# Electrotactile_Schematic.net
KiCad netlist of a schematic drawn in EAGLE
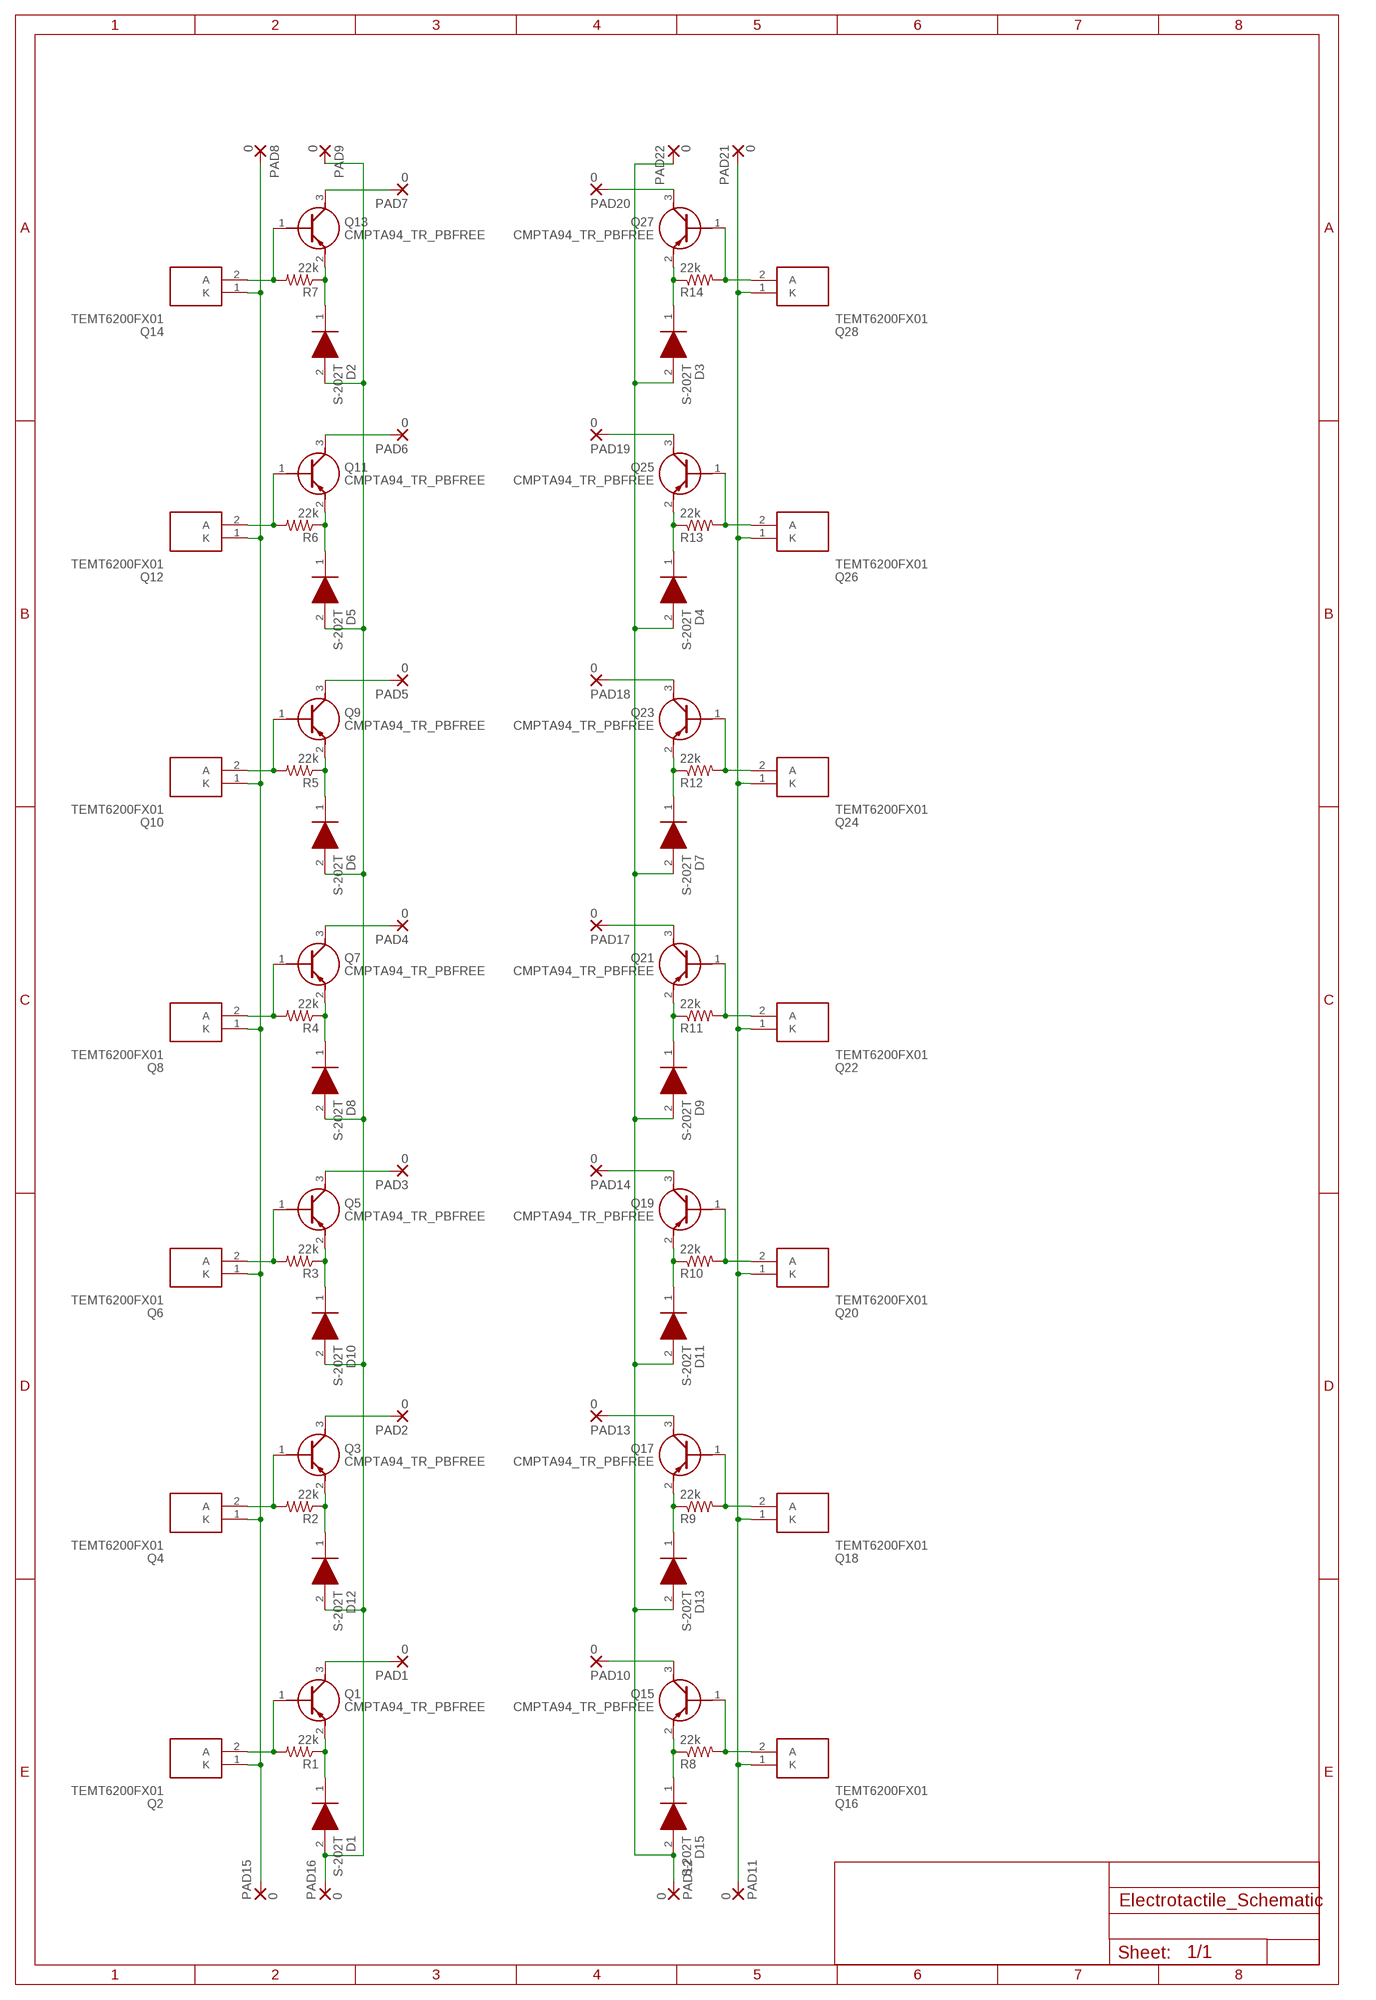
[diagram p0: schematic, sheet 1]

(export (version "E")
  (design (tool "Eeschema 10.0.6"))
  (components
    (comp (ref "D1")
      (value "S-202T")
      (footprint "eagle-import:SODFL3516X70N")
      (fields (field (name "MOUSER_PART_NUMBER") "954-S-202T"))
      (libsource (lib "eagle-import") (part "S-202T"))
    )
    (comp (ref "D2")
      (value "S-202T")
      (footprint "eagle-import:SODFL3516X70N")
      (fields (field (name "MOUSER_PART_NUMBER") "954-S-202T"))
      (libsource (lib "eagle-import") (part "S-202T"))
    )
    (comp (ref "D3")
      (value "S-202T")
      (footprint "eagle-import:SODFL3516X70N")
      (fields (field (name "MOUSER_PART_NUMBER") "954-S-202T"))
      (libsource (lib "eagle-import") (part "S-202T"))
    )
    (comp (ref "D4")
      (value "S-202T")
      (footprint "eagle-import:SODFL3516X70N")
      (fields (field (name "MOUSER_PART_NUMBER") "954-S-202T"))
      (libsource (lib "eagle-import") (part "S-202T"))
    )
    (comp (ref "D5")
      (value "S-202T")
      (footprint "eagle-import:SODFL3516X70N")
      (fields (field (name "MOUSER_PART_NUMBER") "954-S-202T"))
      (libsource (lib "eagle-import") (part "S-202T"))
    )
    (comp (ref "D6")
      (value "S-202T")
      (footprint "eagle-import:SODFL3516X70N")
      (fields (field (name "MOUSER_PART_NUMBER") "954-S-202T"))
      (libsource (lib "eagle-import") (part "S-202T"))
    )
    (comp (ref "D7")
      (value "S-202T")
      (footprint "eagle-import:SODFL3516X70N")
      (fields (field (name "MOUSER_PART_NUMBER") "954-S-202T"))
      (libsource (lib "eagle-import") (part "S-202T"))
    )
    (comp (ref "D8")
      (value "S-202T")
      (footprint "eagle-import:SODFL3516X70N")
      (fields (field (name "MOUSER_PART_NUMBER") "954-S-202T"))
      (libsource (lib "eagle-import") (part "S-202T"))
    )
    (comp (ref "D9")
      (value "S-202T")
      (footprint "eagle-import:SODFL3516X70N")
      (fields (field (name "MOUSER_PART_NUMBER") "954-S-202T"))
      (libsource (lib "eagle-import") (part "S-202T"))
    )
    (comp (ref "D10")
      (value "S-202T")
      (footprint "eagle-import:SODFL3516X70N")
      (fields (field (name "MOUSER_PART_NUMBER") "954-S-202T"))
      (libsource (lib "eagle-import") (part "S-202T"))
    )
    (comp (ref "D11")
      (value "S-202T")
      (footprint "eagle-import:SODFL3516X70N")
      (fields (field (name "MOUSER_PART_NUMBER") "954-S-202T"))
      (libsource (lib "eagle-import") (part "S-202T"))
    )
    (comp (ref "D12")
      (value "S-202T")
      (footprint "eagle-import:SODFL3516X70N")
      (fields (field (name "MOUSER_PART_NUMBER") "954-S-202T"))
      (libsource (lib "eagle-import") (part "S-202T"))
    )
    (comp (ref "D13")
      (value "S-202T")
      (footprint "eagle-import:SODFL3516X70N")
      (fields (field (name "MOUSER_PART_NUMBER") "954-S-202T"))
      (libsource (lib "eagle-import") (part "S-202T"))
    )
    (comp (ref "D15")
      (value "S-202T")
      (footprint "eagle-import:SODFL3516X70N")
      (fields (field (name "MOUSER_PART_NUMBER") "954-S-202T"))
      (libsource (lib "eagle-import") (part "S-202T"))
    )
    (comp (ref "PAD1")
      (value "0")
      (footprint "eagle-import:1,6_0,8")
      (libsource (lib "eagle-import") (part "1,6/0,8"))
    )
    (comp (ref "PAD2")
      (value "0")
      (footprint "eagle-import:1,6_0,8")
      (libsource (lib "eagle-import") (part "1,6/0,8"))
    )
    (comp (ref "PAD3")
      (value "0")
      (footprint "eagle-import:1,6_0,8")
      (libsource (lib "eagle-import") (part "1,6/0,8"))
    )
    (comp (ref "PAD4")
      (value "0")
      (footprint "eagle-import:1,6_0,8")
      (libsource (lib "eagle-import") (part "1,6/0,8"))
    )
    (comp (ref "PAD5")
      (value "0")
      (footprint "eagle-import:1,6_0,8")
      (libsource (lib "eagle-import") (part "1,6/0,8"))
    )
    (comp (ref "PAD6")
      (value "0")
      (footprint "eagle-import:1,6_0,8")
      (libsource (lib "eagle-import") (part "1,6/0,8"))
    )
    (comp (ref "PAD7")
      (value "0")
      (footprint "eagle-import:1,6_0,8")
      (libsource (lib "eagle-import") (part "1,6/0,8"))
    )
    (comp (ref "PAD8")
      (value "0")
      (footprint "eagle-import:1,6_0,8")
      (libsource (lib "eagle-import") (part "1,6/0,8"))
    )
    (comp (ref "PAD9")
      (value "0")
      (footprint "eagle-import:1,6_0,8")
      (libsource (lib "eagle-import") (part "1,6/0,8"))
    )
    (comp (ref "PAD10")
      (value "0")
      (footprint "eagle-import:1,6_0,8")
      (libsource (lib "eagle-import") (part "1,6/0,8"))
    )
    (comp (ref "PAD11")
      (value "0")
      (footprint "eagle-import:1,6_0,8")
      (libsource (lib "eagle-import") (part "1,6/0,8"))
    )
    (comp (ref "PAD12")
      (value "0")
      (footprint "eagle-import:1,6_0,8")
      (libsource (lib "eagle-import") (part "1,6/0,8"))
    )
    (comp (ref "PAD13")
      (value "0")
      (footprint "eagle-import:1,6_0,8")
      (libsource (lib "eagle-import") (part "1,6/0,8"))
    )
    (comp (ref "PAD14")
      (value "0")
      (footprint "eagle-import:1,6_0,8")
      (libsource (lib "eagle-import") (part "1,6/0,8"))
    )
    (comp (ref "PAD15")
      (value "0")
      (footprint "eagle-import:1,6_0,8")
      (libsource (lib "eagle-import") (part "1,6/0,8"))
    )
    (comp (ref "PAD16")
      (value "0")
      (footprint "eagle-import:1,6_0,8")
      (libsource (lib "eagle-import") (part "1,6/0,8"))
    )
    (comp (ref "PAD17")
      (value "0")
      (footprint "eagle-import:1,6_0,8")
      (libsource (lib "eagle-import") (part "1,6/0,8"))
    )
    (comp (ref "PAD18")
      (value "0")
      (footprint "eagle-import:1,6_0,8")
      (libsource (lib "eagle-import") (part "1,6/0,8"))
    )
    (comp (ref "PAD19")
      (value "0")
      (footprint "eagle-import:1,6_0,8")
      (libsource (lib "eagle-import") (part "1,6/0,8"))
    )
    (comp (ref "PAD20")
      (value "0")
      (footprint "eagle-import:1,6_0,8")
      (libsource (lib "eagle-import") (part "1,6/0,8"))
    )
    (comp (ref "PAD21")
      (value "0")
      (footprint "eagle-import:1,6_0,8")
      (libsource (lib "eagle-import") (part "1,6/0,8"))
    )
    (comp (ref "PAD22")
      (value "0")
      (footprint "eagle-import:1,6_0,8")
      (libsource (lib "eagle-import") (part "1,6/0,8"))
    )
    (comp (ref "Q1")
      (value "CMPTA94_TR_PBFREE")
      (footprint "eagle-import:SOT95P230X109-3N")
      (fields (field (name "MANUFACTURER_PART_NUMBER") "CMPTA94 TR PBFREE"))
      (libsource (lib "eagle-import") (part "CMPTA94_TR_PBFREE"))
    )
    (comp (ref "Q2")
      (value "TEMT6200FX01")
      (footprint "eagle-import:LEDC2012X95N")
      (fields (field (name "MOUSER_PART_NUMBER") "782-TEMT6200F"))
      (libsource (lib "eagle-import") (part "TEMT6200FX01"))
    )
    (comp (ref "Q3")
      (value "CMPTA94_TR_PBFREE")
      (footprint "eagle-import:SOT95P230X109-3N")
      (fields (field (name "MANUFACTURER_PART_NUMBER") "CMPTA94 TR PBFREE"))
      (libsource (lib "eagle-import") (part "CMPTA94_TR_PBFREE"))
    )
    (comp (ref "Q4")
      (value "TEMT6200FX01")
      (footprint "eagle-import:LEDC2012X95N")
      (fields (field (name "MOUSER_PART_NUMBER") "782-TEMT6200F"))
      (libsource (lib "eagle-import") (part "TEMT6200FX01"))
    )
    (comp (ref "Q5")
      (value "CMPTA94_TR_PBFREE")
      (footprint "eagle-import:SOT95P230X109-3N")
      (fields (field (name "MANUFACTURER_PART_NUMBER") "CMPTA94 TR PBFREE"))
      (libsource (lib "eagle-import") (part "CMPTA94_TR_PBFREE"))
    )
    (comp (ref "Q6")
      (value "TEMT6200FX01")
      (footprint "eagle-import:LEDC2012X95N")
      (fields (field (name "MOUSER_PART_NUMBER") "782-TEMT6200F"))
      (libsource (lib "eagle-import") (part "TEMT6200FX01"))
    )
    (comp (ref "Q7")
      (value "CMPTA94_TR_PBFREE")
      (footprint "eagle-import:SOT95P230X109-3N")
      (fields (field (name "MANUFACTURER_PART_NUMBER") "CMPTA94 TR PBFREE"))
      (libsource (lib "eagle-import") (part "CMPTA94_TR_PBFREE"))
    )
    (comp (ref "Q8")
      (value "TEMT6200FX01")
      (footprint "eagle-import:LEDC2012X95N")
      (fields (field (name "MOUSER_PART_NUMBER") "782-TEMT6200F"))
      (libsource (lib "eagle-import") (part "TEMT6200FX01"))
    )
    (comp (ref "Q9")
      (value "CMPTA94_TR_PBFREE")
      (footprint "eagle-import:SOT95P230X109-3N")
      (fields (field (name "MANUFACTURER_PART_NUMBER") "CMPTA94 TR PBFREE"))
      (libsource (lib "eagle-import") (part "CMPTA94_TR_PBFREE"))
    )
    (comp (ref "Q10")
      (value "TEMT6200FX01")
      (footprint "eagle-import:LEDC2012X95N")
      (fields (field (name "MOUSER_PART_NUMBER") "782-TEMT6200F"))
      (libsource (lib "eagle-import") (part "TEMT6200FX01"))
    )
    (comp (ref "Q11")
      (value "CMPTA94_TR_PBFREE")
      (footprint "eagle-import:SOT95P230X109-3N")
      (fields (field (name "MANUFACTURER_PART_NUMBER") "CMPTA94 TR PBFREE"))
      (libsource (lib "eagle-import") (part "CMPTA94_TR_PBFREE"))
    )
    (comp (ref "Q12")
      (value "TEMT6200FX01")
      (footprint "eagle-import:LEDC2012X95N")
      (fields (field (name "MOUSER_PART_NUMBER") "782-TEMT6200F"))
      (libsource (lib "eagle-import") (part "TEMT6200FX01"))
    )
    (comp (ref "Q13")
      (value "CMPTA94_TR_PBFREE")
      (footprint "eagle-import:SOT95P230X109-3N")
      (fields (field (name "MANUFACTURER_PART_NUMBER") "CMPTA94 TR PBFREE"))
      (libsource (lib "eagle-import") (part "CMPTA94_TR_PBFREE"))
    )
    (comp (ref "Q14")
      (value "TEMT6200FX01")
      (footprint "eagle-import:LEDC2012X95N")
      (fields (field (name "MOUSER_PART_NUMBER") "782-TEMT6200F"))
      (libsource (lib "eagle-import") (part "TEMT6200FX01"))
    )
    (comp (ref "Q15")
      (value "CMPTA94_TR_PBFREE")
      (footprint "eagle-import:SOT95P230X109-3N")
      (fields (field (name "MANUFACTURER_PART_NUMBER") "CMPTA94 TR PBFREE"))
      (libsource (lib "eagle-import") (part "CMPTA94_TR_PBFREE"))
    )
    (comp (ref "Q16")
      (value "TEMT6200FX01")
      (footprint "eagle-import:LEDC2012X95N")
      (fields (field (name "MOUSER_PART_NUMBER") "782-TEMT6200F"))
      (libsource (lib "eagle-import") (part "TEMT6200FX01"))
    )
    (comp (ref "Q17")
      (value "CMPTA94_TR_PBFREE")
      (footprint "eagle-import:SOT95P230X109-3N")
      (fields (field (name "MANUFACTURER_PART_NUMBER") "CMPTA94 TR PBFREE"))
      (libsource (lib "eagle-import") (part "CMPTA94_TR_PBFREE"))
    )
    (comp (ref "Q18")
      (value "TEMT6200FX01")
      (footprint "eagle-import:LEDC2012X95N")
      (fields (field (name "MOUSER_PART_NUMBER") "782-TEMT6200F"))
      (libsource (lib "eagle-import") (part "TEMT6200FX01"))
    )
    (comp (ref "Q19")
      (value "CMPTA94_TR_PBFREE")
      (footprint "eagle-import:SOT95P230X109-3N")
      (fields (field (name "MANUFACTURER_PART_NUMBER") "CMPTA94 TR PBFREE"))
      (libsource (lib "eagle-import") (part "CMPTA94_TR_PBFREE"))
    )
    (comp (ref "Q20")
      (value "TEMT6200FX01")
      (footprint "eagle-import:LEDC2012X95N")
      (fields (field (name "MOUSER_PART_NUMBER") "782-TEMT6200F"))
      (libsource (lib "eagle-import") (part "TEMT6200FX01"))
    )
    (comp (ref "Q21")
      (value "CMPTA94_TR_PBFREE")
      (footprint "eagle-import:SOT95P230X109-3N")
      (fields (field (name "MANUFACTURER_PART_NUMBER") "CMPTA94 TR PBFREE"))
      (libsource (lib "eagle-import") (part "CMPTA94_TR_PBFREE"))
    )
    (comp (ref "Q22")
      (value "TEMT6200FX01")
      (footprint "eagle-import:LEDC2012X95N")
      (fields (field (name "MOUSER_PART_NUMBER") "782-TEMT6200F"))
      (libsource (lib "eagle-import") (part "TEMT6200FX01"))
    )
    (comp (ref "Q23")
      (value "CMPTA94_TR_PBFREE")
      (footprint "eagle-import:SOT95P230X109-3N")
      (fields (field (name "MANUFACTURER_PART_NUMBER") "CMPTA94 TR PBFREE"))
      (libsource (lib "eagle-import") (part "CMPTA94_TR_PBFREE"))
    )
    (comp (ref "Q24")
      (value "TEMT6200FX01")
      (footprint "eagle-import:LEDC2012X95N")
      (fields (field (name "MOUSER_PART_NUMBER") "782-TEMT6200F"))
      (libsource (lib "eagle-import") (part "TEMT6200FX01"))
    )
    (comp (ref "Q25")
      (value "CMPTA94_TR_PBFREE")
      (footprint "eagle-import:SOT95P230X109-3N")
      (fields (field (name "MANUFACTURER_PART_NUMBER") "CMPTA94 TR PBFREE"))
      (libsource (lib "eagle-import") (part "CMPTA94_TR_PBFREE"))
    )
    (comp (ref "Q26")
      (value "TEMT6200FX01")
      (footprint "eagle-import:LEDC2012X95N")
      (fields (field (name "MOUSER_PART_NUMBER") "782-TEMT6200F"))
      (libsource (lib "eagle-import") (part "TEMT6200FX01"))
    )
    (comp (ref "Q27")
      (value "CMPTA94_TR_PBFREE")
      (footprint "eagle-import:SOT95P230X109-3N")
      (fields (field (name "MANUFACTURER_PART_NUMBER") "CMPTA94 TR PBFREE"))
      (libsource (lib "eagle-import") (part "CMPTA94_TR_PBFREE"))
    )
    (comp (ref "Q28")
      (value "TEMT6200FX01")
      (footprint "eagle-import:LEDC2012X95N")
      (fields (field (name "MOUSER_PART_NUMBER") "782-TEMT6200F"))
      (libsource (lib "eagle-import") (part "TEMT6200FX01"))
    )
    (comp (ref "R1")
      (value "22k")
      (footprint "eagle-import:R0805")
      (libsource (lib "eagle-import") (part "R-US_R0805"))
    )
    (comp (ref "R2")
      (value "22k")
      (footprint "eagle-import:R0805")
      (libsource (lib "eagle-import") (part "R-US_R0805"))
    )
    (comp (ref "R3")
      (value "22k")
      (footprint "eagle-import:R0805")
      (libsource (lib "eagle-import") (part "R-US_R0805"))
    )
    (comp (ref "R4")
      (value "22k")
      (footprint "eagle-import:R0805")
      (libsource (lib "eagle-import") (part "R-US_R0805"))
    )
    (comp (ref "R5")
      (value "22k")
      (footprint "eagle-import:R0805")
      (libsource (lib "eagle-import") (part "R-US_R0805"))
    )
    (comp (ref "R6")
      (value "22k")
      (footprint "eagle-import:R0805")
      (libsource (lib "eagle-import") (part "R-US_R0805"))
    )
    (comp (ref "R7")
      (value "22k")
      (footprint "eagle-import:R0805")
      (libsource (lib "eagle-import") (part "R-US_R0805"))
    )
    (comp (ref "R8")
      (value "22k")
      (footprint "eagle-import:R0805")
      (libsource (lib "eagle-import") (part "R-US_R0805"))
    )
    (comp (ref "R9")
      (value "22k")
      (footprint "eagle-import:R0805")
      (libsource (lib "eagle-import") (part "R-US_R0805"))
    )
    (comp (ref "R10")
      (value "22k")
      (footprint "eagle-import:R0805")
      (libsource (lib "eagle-import") (part "R-US_R0805"))
    )
    (comp (ref "R11")
      (value "22k")
      (footprint "eagle-import:R0805")
      (libsource (lib "eagle-import") (part "R-US_R0805"))
    )
    (comp (ref "R12")
      (value "22k")
      (footprint "eagle-import:R0805")
      (libsource (lib "eagle-import") (part "R-US_R0805"))
    )
    (comp (ref "R13")
      (value "22k")
      (footprint "eagle-import:R0805")
      (libsource (lib "eagle-import") (part "R-US_R0805"))
    )
    (comp (ref "R14")
      (value "22k")
      (footprint "eagle-import:R0805")
      (libsource (lib "eagle-import") (part "R-US_R0805"))
    )
  )
  (nets
    (net (code "1") (name "Net-(D1-A)") (class "Default")
      (node (ref "D1") (pin "2") (pinfunction "A_2") (pintype "bidirectional"))
      (node (ref "D10") (pin "2") (pinfunction "A_2") (pintype "bidirectional"))
      (node (ref "D12") (pin "2") (pinfunction "A_2") (pintype "bidirectional"))
      (node (ref "D2") (pin "2") (pinfunction "A_2") (pintype "bidirectional"))
      (node (ref "D5") (pin "2") (pinfunction "A_2") (pintype "bidirectional"))
      (node (ref "D6") (pin "2") (pinfunction "A_2") (pintype "bidirectional"))
      (node (ref "D8") (pin "2") (pinfunction "A_2") (pintype "bidirectional"))
      (node (ref "PAD16") (pin "1") (pinfunction "P_1") (pintype "passive"))
      (node (ref "PAD9") (pin "1") (pinfunction "P_1") (pintype "passive"))
    )
    (net (code "2") (name "Net-(D1-K)") (class "Default")
      (node (ref "D1") (pin "1") (pinfunction "K_1") (pintype "bidirectional"))
      (node (ref "Q1") (pin "2") (pinfunction "E_2") (pintype "bidirectional"))
      (node (ref "R1") (pin "1") (pinfunction "1_1") (pintype "passive"))
    )
    (net (code "3") (name "Net-(D2-K)") (class "Default")
      (node (ref "D2") (pin "1") (pinfunction "K_1") (pintype "bidirectional"))
      (node (ref "Q13") (pin "2") (pinfunction "E_2") (pintype "bidirectional"))
      (node (ref "R7") (pin "1") (pinfunction "1_1") (pintype "passive"))
    )
    (net (code "4") (name "Net-(D3-K)") (class "Default")
      (node (ref "D3") (pin "1") (pinfunction "K_1") (pintype "bidirectional"))
      (node (ref "Q27") (pin "2") (pinfunction "E_2") (pintype "bidirectional"))
      (node (ref "R14") (pin "1") (pinfunction "1_1") (pintype "passive"))
    )
    (net (code "5") (name "Net-(D4-K)") (class "Default")
      (node (ref "D4") (pin "1") (pinfunction "K_1") (pintype "bidirectional"))
      (node (ref "Q25") (pin "2") (pinfunction "E_2") (pintype "bidirectional"))
      (node (ref "R13") (pin "1") (pinfunction "1_1") (pintype "passive"))
    )
    (net (code "6") (name "Net-(D5-K)") (class "Default")
      (node (ref "D5") (pin "1") (pinfunction "K_1") (pintype "bidirectional"))
      (node (ref "Q11") (pin "2") (pinfunction "E_2") (pintype "bidirectional"))
      (node (ref "R6") (pin "1") (pinfunction "1_1") (pintype "passive"))
    )
    (net (code "7") (name "Net-(D6-K)") (class "Default")
      (node (ref "D6") (pin "1") (pinfunction "K_1") (pintype "bidirectional"))
      (node (ref "Q9") (pin "2") (pinfunction "E_2") (pintype "bidirectional"))
      (node (ref "R5") (pin "1") (pinfunction "1_1") (pintype "passive"))
    )
    (net (code "8") (name "Net-(D7-K)") (class "Default")
      (node (ref "D7") (pin "1") (pinfunction "K_1") (pintype "bidirectional"))
      (node (ref "Q23") (pin "2") (pinfunction "E_2") (pintype "bidirectional"))
      (node (ref "R12") (pin "1") (pinfunction "1_1") (pintype "passive"))
    )
    (net (code "9") (name "Net-(D8-K)") (class "Default")
      (node (ref "D8") (pin "1") (pinfunction "K_1") (pintype "bidirectional"))
      (node (ref "Q7") (pin "2") (pinfunction "E_2") (pintype "bidirectional"))
      (node (ref "R4") (pin "1") (pinfunction "1_1") (pintype "passive"))
    )
    (net (code "10") (name "Net-(D9-K)") (class "Default")
      (node (ref "D9") (pin "1") (pinfunction "K_1") (pintype "bidirectional"))
      (node (ref "Q21") (pin "2") (pinfunction "E_2") (pintype "bidirectional"))
      (node (ref "R11") (pin "1") (pinfunction "1_1") (pintype "passive"))
    )
    (net (code "11") (name "Net-(D10-K)") (class "Default")
      (node (ref "D10") (pin "1") (pinfunction "K_1") (pintype "bidirectional"))
      (node (ref "Q5") (pin "2") (pinfunction "E_2") (pintype "bidirectional"))
      (node (ref "R3") (pin "1") (pinfunction "1_1") (pintype "passive"))
    )
    (net (code "12") (name "Net-(D11-A)") (class "Default")
      (node (ref "D11") (pin "2") (pinfunction "A_2") (pintype "bidirectional"))
      (node (ref "D13") (pin "2") (pinfunction "A_2") (pintype "bidirectional"))
      (node (ref "D15") (pin "2") (pinfunction "A_2") (pintype "bidirectional"))
      (node (ref "D3") (pin "2") (pinfunction "A_2") (pintype "bidirectional"))
      (node (ref "D4") (pin "2") (pinfunction "A_2") (pintype "bidirectional"))
      (node (ref "D7") (pin "2") (pinfunction "A_2") (pintype "bidirectional"))
      (node (ref "D9") (pin "2") (pinfunction "A_2") (pintype "bidirectional"))
      (node (ref "PAD12") (pin "1") (pinfunction "P_1") (pintype "passive"))
      (node (ref "PAD22") (pin "1") (pinfunction "P_1") (pintype "passive"))
    )
    (net (code "13") (name "Net-(D11-K)") (class "Default")
      (node (ref "D11") (pin "1") (pinfunction "K_1") (pintype "bidirectional"))
      (node (ref "Q19") (pin "2") (pinfunction "E_2") (pintype "bidirectional"))
      (node (ref "R10") (pin "1") (pinfunction "1_1") (pintype "passive"))
    )
    (net (code "14") (name "Net-(D12-K)") (class "Default")
      (node (ref "D12") (pin "1") (pinfunction "K_1") (pintype "bidirectional"))
      (node (ref "Q3") (pin "2") (pinfunction "E_2") (pintype "bidirectional"))
      (node (ref "R2") (pin "1") (pinfunction "1_1") (pintype "passive"))
    )
    (net (code "15") (name "Net-(D13-K)") (class "Default")
      (node (ref "D13") (pin "1") (pinfunction "K_1") (pintype "bidirectional"))
      (node (ref "Q17") (pin "2") (pinfunction "E_2") (pintype "bidirectional"))
      (node (ref "R9") (pin "1") (pinfunction "1_1") (pintype "passive"))
    )
    (net (code "16") (name "Net-(D15-K)") (class "Default")
      (node (ref "D15") (pin "1") (pinfunction "K_1") (pintype "bidirectional"))
      (node (ref "Q15") (pin "2") (pinfunction "E_2") (pintype "bidirectional"))
      (node (ref "R8") (pin "1") (pinfunction "1_1") (pintype "passive"))
    )
    (net (code "17") (name "Net-(PAD1-P)") (class "Default")
      (node (ref "PAD1") (pin "1") (pinfunction "P_1") (pintype "passive"))
      (node (ref "Q1") (pin "3") (pinfunction "C_3") (pintype "bidirectional"))
    )
    (net (code "18") (name "Net-(PAD2-P)") (class "Default")
      (node (ref "PAD2") (pin "1") (pinfunction "P_1") (pintype "passive"))
      (node (ref "Q3") (pin "3") (pinfunction "C_3") (pintype "bidirectional"))
    )
    (net (code "19") (name "Net-(PAD3-P)") (class "Default")
      (node (ref "PAD3") (pin "1") (pinfunction "P_1") (pintype "passive"))
      (node (ref "Q5") (pin "3") (pinfunction "C_3") (pintype "bidirectional"))
    )
    (net (code "20") (name "Net-(PAD4-P)") (class "Default")
      (node (ref "PAD4") (pin "1") (pinfunction "P_1") (pintype "passive"))
      (node (ref "Q7") (pin "3") (pinfunction "C_3") (pintype "bidirectional"))
    )
    (net (code "21") (name "Net-(PAD5-P)") (class "Default")
      (node (ref "PAD5") (pin "1") (pinfunction "P_1") (pintype "passive"))
      (node (ref "Q9") (pin "3") (pinfunction "C_3") (pintype "bidirectional"))
    )
    (net (code "22") (name "Net-(PAD6-P)") (class "Default")
      (node (ref "PAD6") (pin "1") (pinfunction "P_1") (pintype "passive"))
      (node (ref "Q11") (pin "3") (pinfunction "C_3") (pintype "bidirectional"))
    )
    (net (code "23") (name "Net-(PAD7-P)") (class "Default")
      (node (ref "PAD7") (pin "1") (pinfunction "P_1") (pintype "passive"))
      (node (ref "Q13") (pin "3") (pinfunction "C_3") (pintype "bidirectional"))
    )
    (net (code "24") (name "Net-(PAD10-P)") (class "Default")
      (node (ref "PAD10") (pin "1") (pinfunction "P_1") (pintype "passive"))
      (node (ref "Q15") (pin "3") (pinfunction "C_3") (pintype "bidirectional"))
    )
    (net (code "25") (name "Net-(PAD11-P)") (class "Default")
      (node (ref "PAD11") (pin "1") (pinfunction "P_1") (pintype "passive"))
      (node (ref "PAD21") (pin "1") (pinfunction "P_1") (pintype "passive"))
      (node (ref "Q16") (pin "1") (pinfunction "K_1") (pintype "bidirectional"))
      (node (ref "Q18") (pin "1") (pinfunction "K_1") (pintype "bidirectional"))
      (node (ref "Q20") (pin "1") (pinfunction "K_1") (pintype "bidirectional"))
      (node (ref "Q22") (pin "1") (pinfunction "K_1") (pintype "bidirectional"))
      (node (ref "Q24") (pin "1") (pinfunction "K_1") (pintype "bidirectional"))
      (node (ref "Q26") (pin "1") (pinfunction "K_1") (pintype "bidirectional"))
      (node (ref "Q28") (pin "1") (pinfunction "K_1") (pintype "bidirectional"))
    )
    (net (code "26") (name "Net-(PAD13-P)") (class "Default")
      (node (ref "PAD13") (pin "1") (pinfunction "P_1") (pintype "passive"))
      (node (ref "Q17") (pin "3") (pinfunction "C_3") (pintype "bidirectional"))
    )
    (net (code "27") (name "Net-(PAD14-P)") (class "Default")
      (node (ref "PAD14") (pin "1") (pinfunction "P_1") (pintype "passive"))
      (node (ref "Q19") (pin "3") (pinfunction "C_3") (pintype "bidirectional"))
    )
    (net (code "28") (name "Net-(PAD15-P)") (class "Default")
      (node (ref "PAD15") (pin "1") (pinfunction "P_1") (pintype "passive"))
      (node (ref "PAD8") (pin "1") (pinfunction "P_1") (pintype "passive"))
      (node (ref "Q10") (pin "1") (pinfunction "K_1") (pintype "bidirectional"))
      (node (ref "Q12") (pin "1") (pinfunction "K_1") (pintype "bidirectional"))
      (node (ref "Q14") (pin "1") (pinfunction "K_1") (pintype "bidirectional"))
      (node (ref "Q2") (pin "1") (pinfunction "K_1") (pintype "bidirectional"))
      (node (ref "Q4") (pin "1") (pinfunction "K_1") (pintype "bidirectional"))
      (node (ref "Q6") (pin "1") (pinfunction "K_1") (pintype "bidirectional"))
      (node (ref "Q8") (pin "1") (pinfunction "K_1") (pintype "bidirectional"))
    )
    (net (code "29") (name "Net-(PAD17-P)") (class "Default")
      (node (ref "PAD17") (pin "1") (pinfunction "P_1") (pintype "passive"))
      (node (ref "Q21") (pin "3") (pinfunction "C_3") (pintype "bidirectional"))
    )
    (net (code "30") (name "Net-(PAD18-P)") (class "Default")
      (node (ref "PAD18") (pin "1") (pinfunction "P_1") (pintype "passive"))
      (node (ref "Q23") (pin "3") (pinfunction "C_3") (pintype "bidirectional"))
    )
    (net (code "31") (name "Net-(PAD19-P)") (class "Default")
      (node (ref "PAD19") (pin "1") (pinfunction "P_1") (pintype "passive"))
      (node (ref "Q25") (pin "3") (pinfunction "C_3") (pintype "bidirectional"))
    )
    (net (code "32") (name "Net-(PAD20-P)") (class "Default")
      (node (ref "PAD20") (pin "1") (pinfunction "P_1") (pintype "passive"))
      (node (ref "Q27") (pin "3") (pinfunction "C_3") (pintype "bidirectional"))
    )
    (net (code "33") (name "Net-(Q1-B)") (class "Default")
      (node (ref "Q1") (pin "1") (pinfunction "B_1") (pintype "bidirectional"))
      (node (ref "Q2") (pin "2") (pinfunction "A_2") (pintype "bidirectional"))
      (node (ref "R1") (pin "2") (pinfunction "2_2") (pintype "passive"))
    )
    (net (code "34") (name "Net-(Q3-B)") (class "Default")
      (node (ref "Q3") (pin "1") (pinfunction "B_1") (pintype "bidirectional"))
      (node (ref "Q4") (pin "2") (pinfunction "A_2") (pintype "bidirectional"))
      (node (ref "R2") (pin "2") (pinfunction "2_2") (pintype "passive"))
    )
    (net (code "35") (name "Net-(Q5-B)") (class "Default")
      (node (ref "Q5") (pin "1") (pinfunction "B_1") (pintype "bidirectional"))
      (node (ref "Q6") (pin "2") (pinfunction "A_2") (pintype "bidirectional"))
      (node (ref "R3") (pin "2") (pinfunction "2_2") (pintype "passive"))
    )
    (net (code "36") (name "Net-(Q7-B)") (class "Default")
      (node (ref "Q7") (pin "1") (pinfunction "B_1") (pintype "bidirectional"))
      (node (ref "Q8") (pin "2") (pinfunction "A_2") (pintype "bidirectional"))
      (node (ref "R4") (pin "2") (pinfunction "2_2") (pintype "passive"))
    )
    (net (code "37") (name "Net-(Q10-A)") (class "Default")
      (node (ref "Q10") (pin "2") (pinfunction "A_2") (pintype "bidirectional"))
      (node (ref "Q9") (pin "1") (pinfunction "B_1") (pintype "bidirectional"))
      (node (ref "R5") (pin "2") (pinfunction "2_2") (pintype "passive"))
    )
    (net (code "38") (name "Net-(Q11-B)") (class "Default")
      (node (ref "Q11") (pin "1") (pinfunction "B_1") (pintype "bidirectional"))
      (node (ref "Q12") (pin "2") (pinfunction "A_2") (pintype "bidirectional"))
      (node (ref "R6") (pin "2") (pinfunction "2_2") (pintype "passive"))
    )
    (net (code "39") (name "Net-(Q13-B)") (class "Default")
      (node (ref "Q13") (pin "1") (pinfunction "B_1") (pintype "bidirectional"))
      (node (ref "Q14") (pin "2") (pinfunction "A_2") (pintype "bidirectional"))
      (node (ref "R7") (pin "2") (pinfunction "2_2") (pintype "passive"))
    )
    (net (code "40") (name "Net-(Q15-B)") (class "Default")
      (node (ref "Q15") (pin "1") (pinfunction "B_1") (pintype "bidirectional"))
      (node (ref "Q16") (pin "2") (pinfunction "A_2") (pintype "bidirectional"))
      (node (ref "R8") (pin "2") (pinfunction "2_2") (pintype "passive"))
    )
    (net (code "41") (name "Net-(Q17-B)") (class "Default")
      (node (ref "Q17") (pin "1") (pinfunction "B_1") (pintype "bidirectional"))
      (node (ref "Q18") (pin "2") (pinfunction "A_2") (pintype "bidirectional"))
      (node (ref "R9") (pin "2") (pinfunction "2_2") (pintype "passive"))
    )
    (net (code "42") (name "Net-(Q19-B)") (class "Default")
      (node (ref "Q19") (pin "1") (pinfunction "B_1") (pintype "bidirectional"))
      (node (ref "Q20") (pin "2") (pinfunction "A_2") (pintype "bidirectional"))
      (node (ref "R10") (pin "2") (pinfunction "2_2") (pintype "passive"))
    )
    (net (code "43") (name "Net-(Q21-B)") (class "Default")
      (node (ref "Q21") (pin "1") (pinfunction "B_1") (pintype "bidirectional"))
      (node (ref "Q22") (pin "2") (pinfunction "A_2") (pintype "bidirectional"))
      (node (ref "R11") (pin "2") (pinfunction "2_2") (pintype "passive"))
    )
    (net (code "44") (name "Net-(Q23-B)") (class "Default")
      (node (ref "Q23") (pin "1") (pinfunction "B_1") (pintype "bidirectional"))
      (node (ref "Q24") (pin "2") (pinfunction "A_2") (pintype "bidirectional"))
      (node (ref "R12") (pin "2") (pinfunction "2_2") (pintype "passive"))
    )
    (net (code "45") (name "Net-(Q25-B)") (class "Default")
      (node (ref "Q25") (pin "1") (pinfunction "B_1") (pintype "bidirectional"))
      (node (ref "Q26") (pin "2") (pinfunction "A_2") (pintype "bidirectional"))
      (node (ref "R13") (pin "2") (pinfunction "2_2") (pintype "passive"))
    )
    (net (code "46") (name "Net-(Q27-B)") (class "Default")
      (node (ref "Q27") (pin "1") (pinfunction "B_1") (pintype "bidirectional"))
      (node (ref "Q28") (pin "2") (pinfunction "A_2") (pintype "bidirectional"))
      (node (ref "R14") (pin "2") (pinfunction "2_2") (pintype "passive"))
    )
  )
)
